# HW2_Schematics.net
KiCad netlist of a schematic drawn in EAGLE
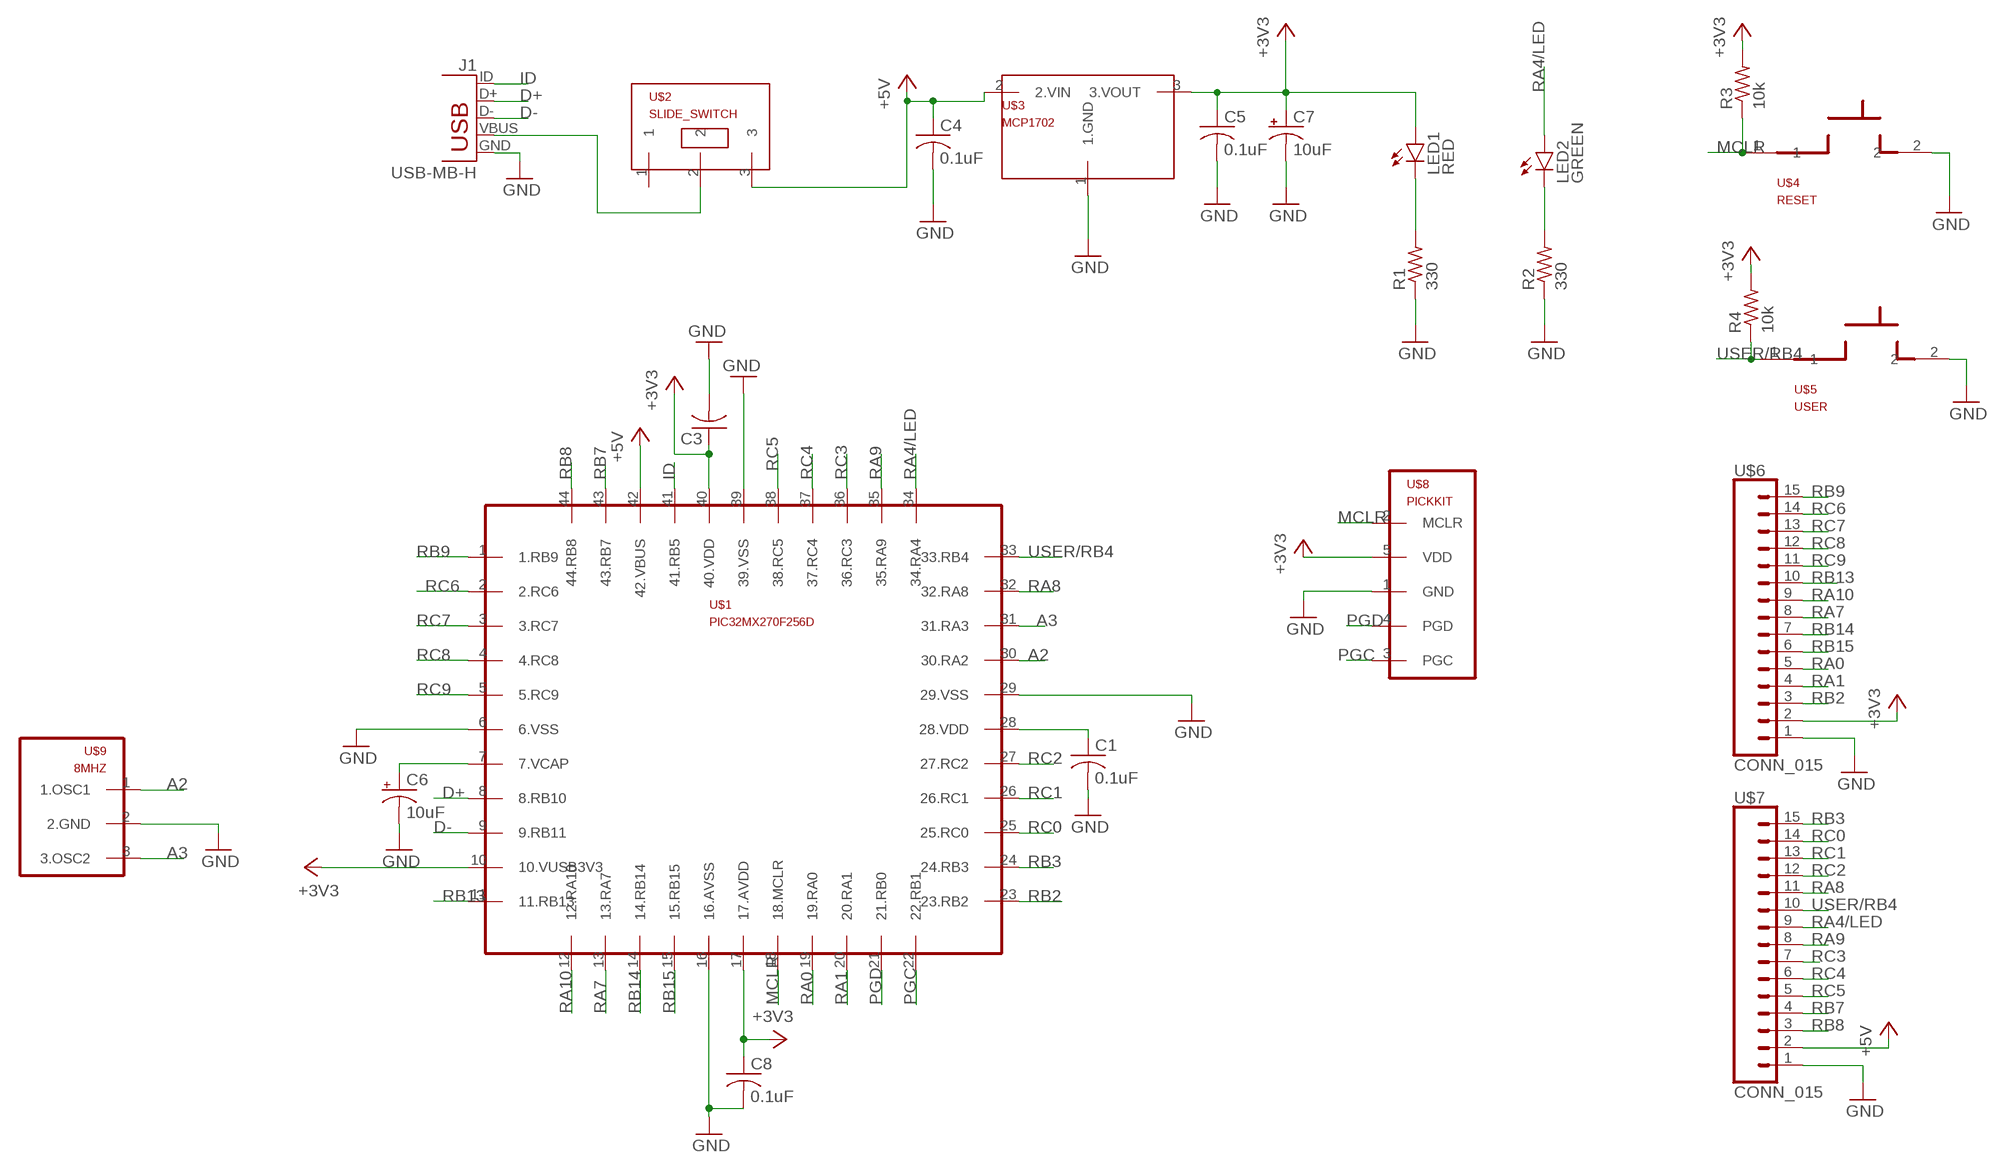
[diagram p0: schematic, sheet 1]

(export (version "E")
  (design (tool "Eeschema 10.0.6"))
  (components
    (comp (ref "C1")
      (value "0.1uF")
      (footprint "eagle-import:C025-025X050")
      (libsource (lib "eagle-import") (part "C-US025-025X050"))
    )
    (comp (ref "C3")
      (value "C-US025-025X050")
      (footprint "eagle-import:C025-025X050")
      (libsource (lib "eagle-import") (part "C-US025-025X050"))
    )
    (comp (ref "C4")
      (value "0.1uF")
      (footprint "eagle-import:C025-025X050")
      (libsource (lib "eagle-import") (part "C-US025-025X050"))
    )
    (comp (ref "C5")
      (value "0.1uF")
      (footprint "eagle-import:C025-025X050")
      (libsource (lib "eagle-import") (part "C-US025-025X050"))
    )
    (comp (ref "C6")
      (value "10uF")
      (footprint "eagle-import:B45181B")
      (libsource (lib "eagle-import") (part "CPOL-USB45181B"))
    )
    (comp (ref "C7")
      (value "10uF")
      (footprint "eagle-import:B45181B")
      (libsource (lib "eagle-import") (part "CPOL-USB45181B"))
    )
    (comp (ref "C8")
      (value "0.1uF")
      (footprint "eagle-import:C025-025X050")
      (libsource (lib "eagle-import") (part "C-US025-025X050"))
    )
    (comp (ref "J1")
      (value "USB-MB-H")
      (footprint "eagle-import:USB-MB-H")
      (libsource (lib "eagle-import") (part "USB-MB-H"))
    )
    (comp (ref "LED1")
      (value "RED")
      (footprint "eagle-import:LED3MM")
      (libsource (lib "eagle-import") (part "LED3MM"))
    )
    (comp (ref "LED2")
      (value "GREEN")
      (footprint "eagle-import:LED3MM")
      (libsource (lib "eagle-import") (part "LED3MM"))
    )
    (comp (ref "R1")
      (value "330")
      (footprint "eagle-import:0207_10")
      (libsource (lib "eagle-import") (part "R-US_0207/10"))
    )
    (comp (ref "R2")
      (value "330")
      (footprint "eagle-import:0207_10")
      (libsource (lib "eagle-import") (part "R-US_0207/10"))
    )
    (comp (ref "R3")
      (value "10k")
      (footprint "eagle-import:0207_10")
      (libsource (lib "eagle-import") (part "R-US_0207/10"))
    )
    (comp (ref "R4")
      (value "10k")
      (footprint "eagle-import:0207_10")
      (libsource (lib "eagle-import") (part "R-US_0207/10"))
    )
    (comp (ref "U$1")
      (value "PIC32MX270F256D")
      (footprint "eagle-import:TQFP44")
      (libsource (lib "eagle-import") (part "PIC32MX270F256D"))
    )
    (comp (ref "U$2")
      (value "SLIDE_SWITCH")
      (footprint "eagle-import:SLIDE_SWITCH")
      (libsource (lib "eagle-import") (part "SLIDE_SWITCH"))
    )
    (comp (ref "U$3")
      (value "MCP1702")
      (footprint "eagle-import:TO92")
      (libsource (lib "eagle-import") (part "MCP1702"))
    )
    (comp (ref "U$4")
      (value "RESET")
      (footprint "eagle-import:PUSHBUTTON")
      (libsource (lib "eagle-import") (part "PUSHBUTTON"))
    )
    (comp (ref "U$5")
      (value "USER")
      (footprint "eagle-import:PUSHBUTTON")
      (libsource (lib "eagle-import") (part "PUSHBUTTON"))
    )
    (comp (ref "U$6")
      (value "CONN_015")
      (footprint "eagle-import:1X15")
      (libsource (lib "eagle-import") (part "CONN_015"))
    )
    (comp (ref "U$7")
      (value "CONN_015")
      (footprint "eagle-import:1X15")
      (libsource (lib "eagle-import") (part "CONN_015"))
    )
    (comp (ref "U$8")
      (value "PICKKIT")
      (footprint "eagle-import:1X05")
      (libsource (lib "eagle-import") (part "PICKKIT"))
    )
    (comp (ref "U$9")
      (value "8MHZ")
      (footprint "eagle-import:OSC")
      (libsource (lib "eagle-import") (part "OSC"))
    )
  )
  (nets
    (net (code "1") (name "+3V3") (class "Default")
      (node (ref "C3") (pin "1") (pinfunction "1_1") (pintype "passive"))
      (node (ref "C5") (pin "1") (pinfunction "1_1") (pintype "passive"))
      (node (ref "C7") (pin "+") (pinfunction "+_+") (pintype "passive"))
      (node (ref "C8") (pin "1") (pinfunction "1_1") (pintype "passive"))
      (node (ref "LED1") (pin "A") (pinfunction "A_A") (pintype "passive"))
      (node (ref "R3") (pin "2") (pinfunction "2_2") (pintype "passive"))
      (node (ref "R4") (pin "2") (pinfunction "2_2") (pintype "passive"))
      (node (ref "U$1") (pin "10") (pinfunction "10.VUSB3V3_10") (pintype "bidirectional"))
      (node (ref "U$1") (pin "17") (pinfunction "17.AVDD_17") (pintype "bidirectional"))
      (node (ref "U$1") (pin "40") (pinfunction "40.VDD_40") (pintype "bidirectional"))
      (node (ref "U$3") (pin "3") (pinfunction "3.VOUT_3") (pintype "bidirectional"))
      (node (ref "U$6") (pin "2") (pinfunction "2_2") (pintype "passive"))
      (node (ref "U$8") (pin "5") (pinfunction "VDD_5") (pintype "bidirectional"))
    )
    (net (code "2") (name "+5V") (class "Default")
      (node (ref "C4") (pin "1") (pinfunction "1_1") (pintype "passive"))
      (node (ref "U$1") (pin "42") (pinfunction "42.VBUS_42") (pintype "bidirectional"))
      (node (ref "U$2") (pin "3") (pinfunction "3_3") (pintype "bidirectional"))
      (node (ref "U$3") (pin "2") (pinfunction "2.VIN_2") (pintype "bidirectional"))
      (node (ref "U$7") (pin "2") (pinfunction "2_2") (pintype "passive"))
    )
    (net (code "3") (name "/A2") (class "Default")
      (node (ref "U$1") (pin "30") (pinfunction "30.RA2_30") (pintype "bidirectional"))
      (node (ref "U$9") (pin "1") (pinfunction "1.OSC1_1") (pintype "bidirectional"))
    )
    (net (code "4") (name "/A3") (class "Default")
      (node (ref "U$1") (pin "31") (pinfunction "31.RA3_31") (pintype "bidirectional"))
      (node (ref "U$9") (pin "3") (pinfunction "3.OSC2_3") (pintype "bidirectional"))
    )
    (net (code "5") (name "/D+") (class "Default")
      (node (ref "J1") (pin "D+") (pinfunction "D+_D+") (pintype "bidirectional"))
      (node (ref "U$1") (pin "8") (pinfunction "8.RB10_8") (pintype "bidirectional"))
    )
    (net (code "6") (name "/D-") (class "Default")
      (node (ref "J1") (pin "D-") (pinfunction "D-_D-") (pintype "bidirectional"))
      (node (ref "U$1") (pin "9") (pinfunction "9.RB11_9") (pintype "bidirectional"))
    )
    (net (code "7") (name "/ID") (class "Default")
      (node (ref "J1") (pin "ID") (pinfunction "ID_ID") (pintype "bidirectional"))
      (node (ref "U$1") (pin "41") (pinfunction "41.RB5_41") (pintype "bidirectional"))
    )
    (net (code "8") (name "/MCLR") (class "Default")
      (node (ref "R3") (pin "1") (pinfunction "1_1") (pintype "passive"))
      (node (ref "U$1") (pin "18") (pinfunction "18.MCLR_18") (pintype "bidirectional"))
      (node (ref "U$4") (pin "1") (pinfunction "1_1") (pintype "bidirectional"))
      (node (ref "U$8") (pin "2") (pinfunction "MCLR_2") (pintype "bidirectional"))
    )
    (net (code "9") (name "/PGC") (class "Default")
      (node (ref "U$1") (pin "22") (pinfunction "22.RB1_22") (pintype "bidirectional"))
      (node (ref "U$8") (pin "3") (pinfunction "PGC_3") (pintype "bidirectional"))
    )
    (net (code "10") (name "/PGD") (class "Default")
      (node (ref "U$1") (pin "21") (pinfunction "21.RB0_21") (pintype "bidirectional"))
      (node (ref "U$8") (pin "4") (pinfunction "PGD_4") (pintype "bidirectional"))
    )
    (net (code "11") (name "/RA0") (class "Default")
      (node (ref "U$1") (pin "19") (pinfunction "19.RA0_19") (pintype "bidirectional"))
      (node (ref "U$6") (pin "5") (pinfunction "5_5") (pintype "passive"))
    )
    (net (code "12") (name "/RA1") (class "Default")
      (node (ref "U$1") (pin "20") (pinfunction "20.RA1_20") (pintype "bidirectional"))
      (node (ref "U$6") (pin "4") (pinfunction "4_4") (pintype "passive"))
    )
    (net (code "13") (name "/RA4{slash}LED") (class "Default")
      (node (ref "LED2") (pin "A") (pinfunction "A_A") (pintype "passive"))
      (node (ref "U$1") (pin "34") (pinfunction "34.RA4_34") (pintype "bidirectional"))
      (node (ref "U$7") (pin "9") (pinfunction "9_9") (pintype "passive"))
    )
    (net (code "14") (name "/RA7") (class "Default")
      (node (ref "U$1") (pin "13") (pinfunction "13.RA7_13") (pintype "bidirectional"))
      (node (ref "U$6") (pin "8") (pinfunction "8_8") (pintype "passive"))
    )
    (net (code "15") (name "/RA8") (class "Default")
      (node (ref "U$1") (pin "32") (pinfunction "32.RA8_32") (pintype "bidirectional"))
      (node (ref "U$7") (pin "11") (pinfunction "11_11") (pintype "passive"))
    )
    (net (code "16") (name "/RA9") (class "Default")
      (node (ref "U$1") (pin "35") (pinfunction "35.RA9_35") (pintype "bidirectional"))
      (node (ref "U$7") (pin "8") (pinfunction "8_8") (pintype "passive"))
    )
    (net (code "17") (name "/RA10") (class "Default")
      (node (ref "U$1") (pin "12") (pinfunction "12.RA10_12") (pintype "bidirectional"))
      (node (ref "U$6") (pin "9") (pinfunction "9_9") (pintype "passive"))
    )
    (net (code "18") (name "/RB2") (class "Default")
      (node (ref "U$1") (pin "23") (pinfunction "23.RB2_23") (pintype "bidirectional"))
      (node (ref "U$6") (pin "3") (pinfunction "3_3") (pintype "passive"))
    )
    (net (code "19") (name "/RB3") (class "Default")
      (node (ref "U$1") (pin "24") (pinfunction "24.RB3_24") (pintype "bidirectional"))
      (node (ref "U$7") (pin "15") (pinfunction "15_15") (pintype "passive"))
    )
    (net (code "20") (name "/RB7") (class "Default")
      (node (ref "U$1") (pin "43") (pinfunction "43.RB7_43") (pintype "bidirectional"))
      (node (ref "U$7") (pin "4") (pinfunction "4_4") (pintype "passive"))
    )
    (net (code "21") (name "/RB8") (class "Default")
      (node (ref "U$1") (pin "44") (pinfunction "44.RB8_44") (pintype "bidirectional"))
      (node (ref "U$7") (pin "3") (pinfunction "3_3") (pintype "passive"))
    )
    (net (code "22") (name "/RB9") (class "Default")
      (node (ref "U$1") (pin "1") (pinfunction "1.RB9_1") (pintype "bidirectional"))
      (node (ref "U$6") (pin "15") (pinfunction "15_15") (pintype "passive"))
    )
    (net (code "23") (name "/RB13") (class "Default")
      (node (ref "U$1") (pin "11") (pinfunction "11.RB13_11") (pintype "bidirectional"))
      (node (ref "U$6") (pin "10") (pinfunction "10_10") (pintype "passive"))
    )
    (net (code "24") (name "/RB14") (class "Default")
      (node (ref "U$1") (pin "14") (pinfunction "14.RB14_14") (pintype "bidirectional"))
      (node (ref "U$6") (pin "7") (pinfunction "7_7") (pintype "passive"))
    )
    (net (code "25") (name "/RB15") (class "Default")
      (node (ref "U$1") (pin "15") (pinfunction "15.RB15_15") (pintype "bidirectional"))
      (node (ref "U$6") (pin "6") (pinfunction "6_6") (pintype "passive"))
    )
    (net (code "26") (name "/RC0") (class "Default")
      (node (ref "U$1") (pin "25") (pinfunction "25.RC0_25") (pintype "bidirectional"))
      (node (ref "U$7") (pin "14") (pinfunction "14_14") (pintype "passive"))
    )
    (net (code "27") (name "/RC1") (class "Default")
      (node (ref "U$1") (pin "26") (pinfunction "26.RC1_26") (pintype "bidirectional"))
      (node (ref "U$7") (pin "13") (pinfunction "13_13") (pintype "passive"))
    )
    (net (code "28") (name "/RC2") (class "Default")
      (node (ref "U$1") (pin "27") (pinfunction "27.RC2_27") (pintype "bidirectional"))
      (node (ref "U$7") (pin "12") (pinfunction "12_12") (pintype "passive"))
    )
    (net (code "29") (name "/RC3") (class "Default")
      (node (ref "U$1") (pin "36") (pinfunction "36.RC3_36") (pintype "bidirectional"))
      (node (ref "U$7") (pin "7") (pinfunction "7_7") (pintype "passive"))
    )
    (net (code "30") (name "/RC4") (class "Default")
      (node (ref "U$1") (pin "37") (pinfunction "37.RC4_37") (pintype "bidirectional"))
      (node (ref "U$7") (pin "6") (pinfunction "6_6") (pintype "passive"))
    )
    (net (code "31") (name "/RC5") (class "Default")
      (node (ref "U$1") (pin "38") (pinfunction "38.RC5_38") (pintype "bidirectional"))
      (node (ref "U$7") (pin "5") (pinfunction "5_5") (pintype "passive"))
    )
    (net (code "32") (name "/RC6") (class "Default")
      (node (ref "U$1") (pin "2") (pinfunction "2.RC6_2") (pintype "bidirectional"))
      (node (ref "U$6") (pin "14") (pinfunction "14_14") (pintype "passive"))
    )
    (net (code "33") (name "/RC7") (class "Default")
      (node (ref "U$1") (pin "3") (pinfunction "3.RC7_3") (pintype "bidirectional"))
      (node (ref "U$6") (pin "13") (pinfunction "13_13") (pintype "passive"))
    )
    (net (code "34") (name "/RC8") (class "Default")
      (node (ref "U$1") (pin "4") (pinfunction "4.RC8_4") (pintype "bidirectional"))
      (node (ref "U$6") (pin "12") (pinfunction "12_12") (pintype "passive"))
    )
    (net (code "35") (name "/RC9") (class "Default")
      (node (ref "U$1") (pin "5") (pinfunction "5.RC9_5") (pintype "bidirectional"))
      (node (ref "U$6") (pin "11") (pinfunction "11_11") (pintype "passive"))
    )
    (net (code "36") (name "/USER{slash}RB4") (class "Default")
      (node (ref "R4") (pin "1") (pinfunction "1_1") (pintype "passive"))
      (node (ref "U$1") (pin "33") (pinfunction "33.RB4_33") (pintype "bidirectional"))
      (node (ref "U$5") (pin "1") (pinfunction "1_1") (pintype "bidirectional"))
      (node (ref "U$7") (pin "10") (pinfunction "10_10") (pintype "passive"))
    )
    (net (code "37") (name "GND") (class "Default")
      (node (ref "C1") (pin "2") (pinfunction "2_2") (pintype "passive"))
      (node (ref "C3") (pin "2") (pinfunction "2_2") (pintype "passive"))
      (node (ref "C4") (pin "2") (pinfunction "2_2") (pintype "passive"))
      (node (ref "C5") (pin "2") (pinfunction "2_2") (pintype "passive"))
      (node (ref "C6") (pin "-") (pinfunction "-_-") (pintype "passive"))
      (node (ref "C7") (pin "-") (pinfunction "-_-") (pintype "passive"))
      (node (ref "C8") (pin "2") (pinfunction "2_2") (pintype "passive"))
      (node (ref "J1") (pin "GND") (pinfunction "GND_GND") (pintype "bidirectional"))
      (node (ref "R1") (pin "1") (pinfunction "1_1") (pintype "passive"))
      (node (ref "R2") (pin "1") (pinfunction "1_1") (pintype "passive"))
      (node (ref "U$1") (pin "16") (pinfunction "16.AVSS_16") (pintype "bidirectional"))
      (node (ref "U$1") (pin "29") (pinfunction "29.VSS_29") (pintype "bidirectional"))
      (node (ref "U$1") (pin "39") (pinfunction "39.VSS_39") (pintype "bidirectional"))
      (node (ref "U$1") (pin "6") (pinfunction "6.VSS_6") (pintype "bidirectional"))
      (node (ref "U$3") (pin "1") (pinfunction "1.GND_1") (pintype "bidirectional"))
      (node (ref "U$4") (pin "2") (pinfunction "2_2") (pintype "bidirectional"))
      (node (ref "U$5") (pin "2") (pinfunction "2_2") (pintype "bidirectional"))
      (node (ref "U$6") (pin "1") (pinfunction "1_1") (pintype "passive"))
      (node (ref "U$7") (pin "1") (pinfunction "1_1") (pintype "passive"))
      (node (ref "U$8") (pin "1") (pinfunction "GND_1") (pintype "bidirectional"))
      (node (ref "U$9") (pin "2") (pinfunction "2.GND_2") (pintype "bidirectional"))
    )
    (net (code "38") (name "Net-(J1-PadVBUS)") (class "Default")
      (node (ref "J1") (pin "VBUS") (pinfunction "VBUS_VBUS") (pintype "bidirectional"))
      (node (ref "U$2") (pin "2") (pinfunction "2_2") (pintype "bidirectional"))
    )
    (net (code "39") (name "Net-(LED1-C)") (class "Default")
      (node (ref "LED1") (pin "K") (pinfunction "C_K") (pintype "passive"))
      (node (ref "R1") (pin "2") (pinfunction "2_2") (pintype "passive"))
    )
    (net (code "40") (name "Net-(LED2-C)") (class "Default")
      (node (ref "LED2") (pin "K") (pinfunction "C_K") (pintype "passive"))
      (node (ref "R2") (pin "2") (pinfunction "2_2") (pintype "passive"))
    )
    (net (code "41") (name "Net-(U$1-7.VCAP)") (class "Default")
      (node (ref "C6") (pin "+") (pinfunction "+_+") (pintype "passive"))
      (node (ref "U$1") (pin "7") (pinfunction "7.VCAP_7") (pintype "bidirectional"))
    )
    (net (code "42") (name "Net-(U$1-28.VDD)") (class "Default")
      (node (ref "C1") (pin "1") (pinfunction "1_1") (pintype "passive"))
      (node (ref "U$1") (pin "28") (pinfunction "28.VDD_28") (pintype "bidirectional"))
    )
    (net (code "43") (name "unconnected-(U$2-Pad1)") (class "Default")
      (node (ref "U$2") (pin "1") (pinfunction "1_1") (pintype "bidirectional"))
    )
  )
)
